# VIC-20_AV-Adaptor.net
KiCad netlist of a schematic drawn in EAGLE
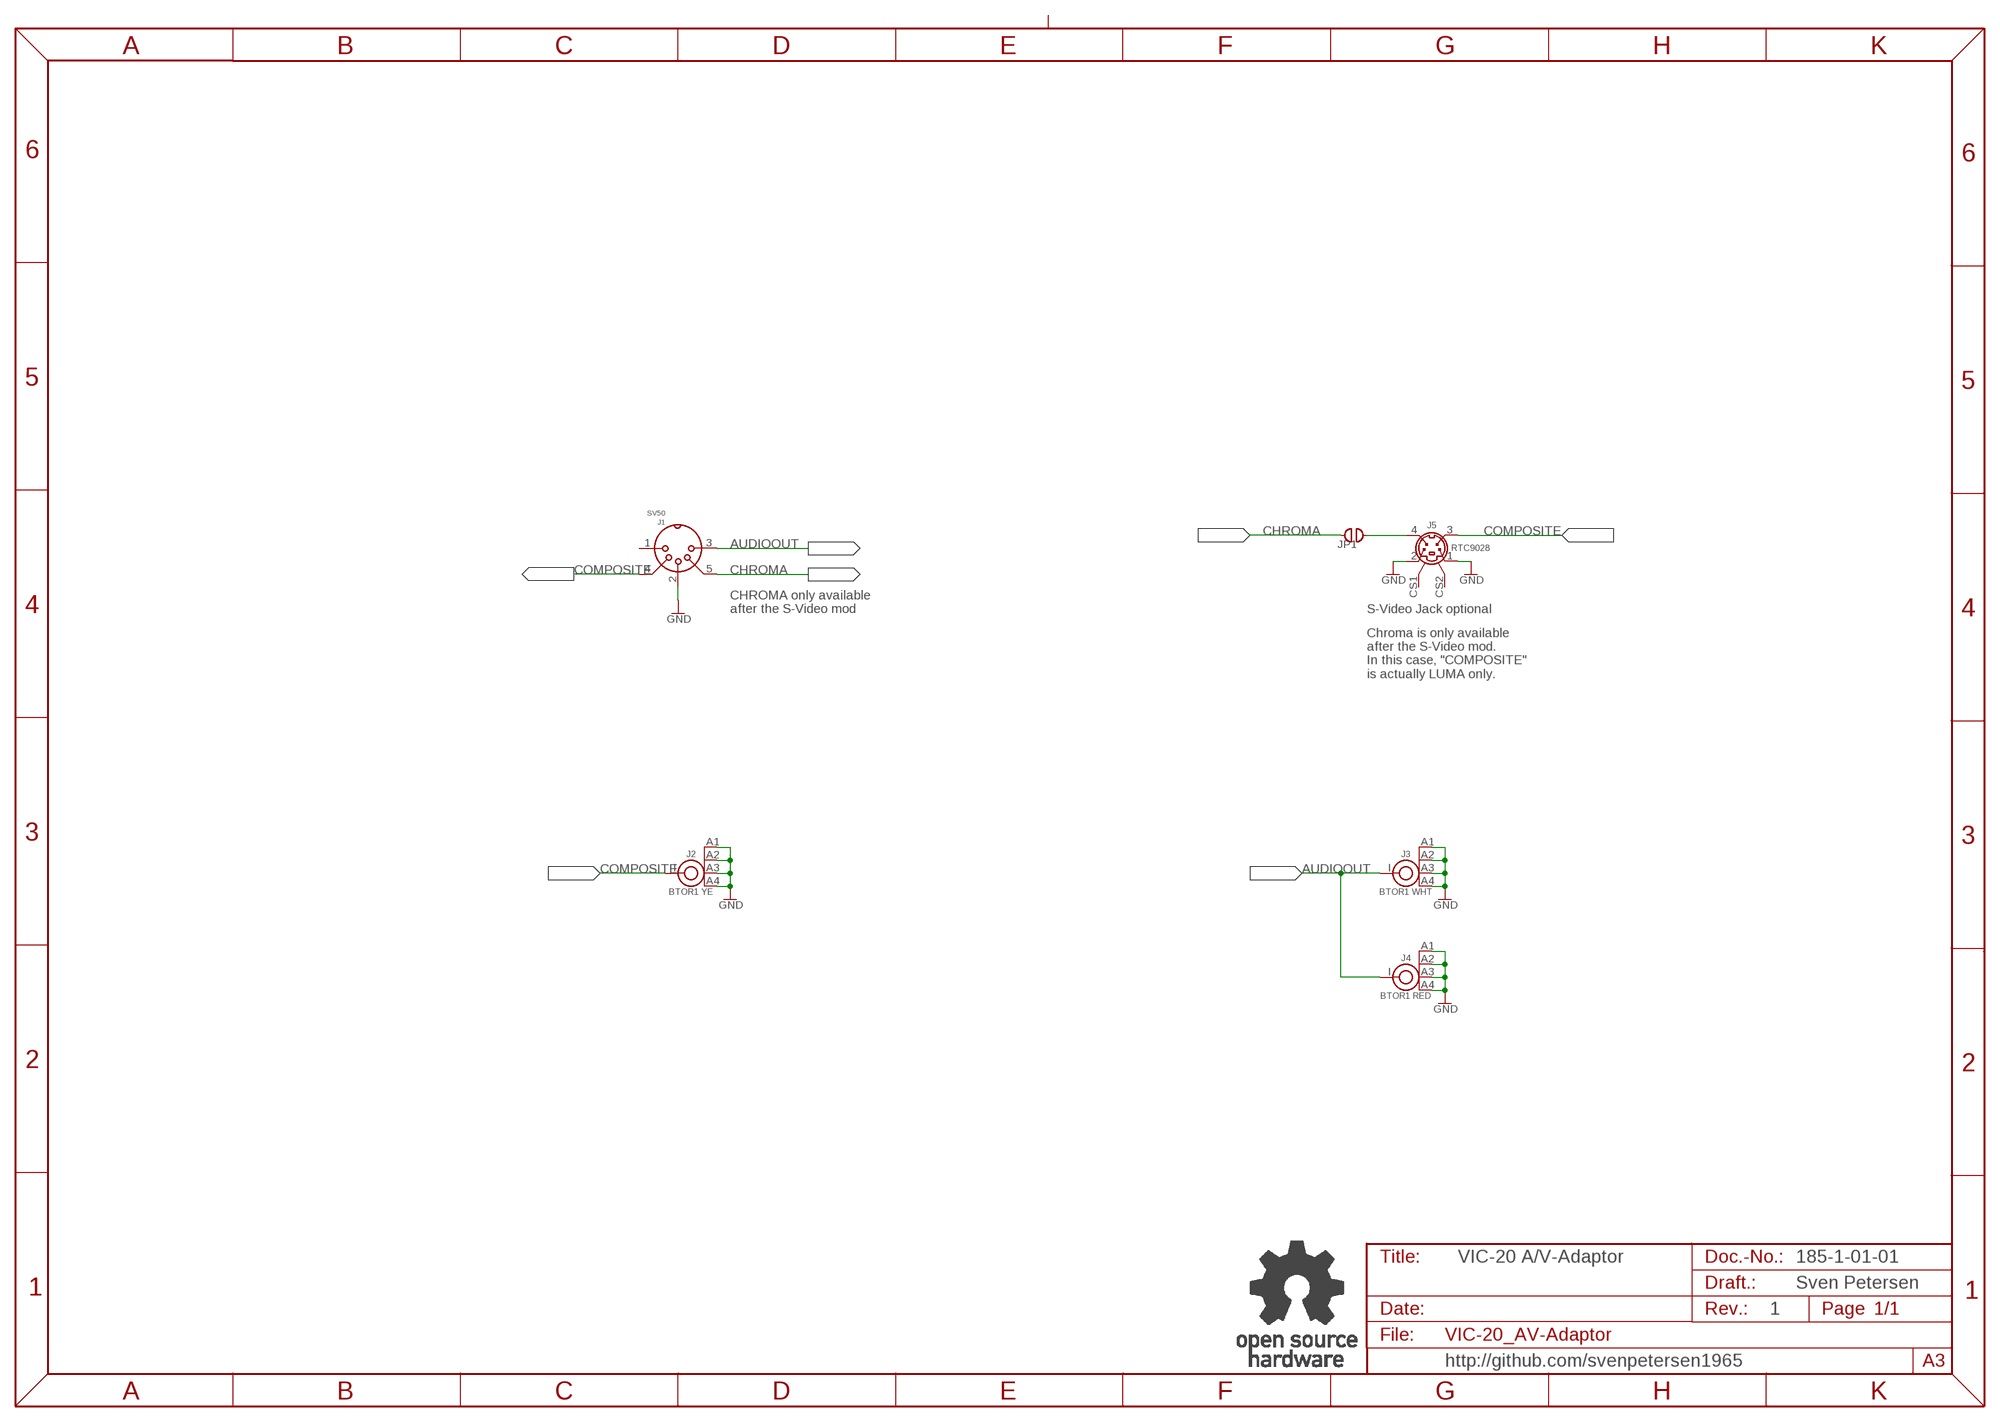
[diagram p0: schematic, sheet 1]

(export (version "E")
  (design (tool "Eeschema 10.0.6"))
  (components
    (comp (ref "J1")
      (value "SV50")
      (footprint "eagle-import:SV50_INNER")
      (libsource (lib "eagle-import") (part "SV50"))
    )
    (comp (ref "J2")
      (value "BTOR1 YE")
      (footprint "eagle-import:BTOR1")
      (libsource (lib "eagle-import") (part "BTOR1"))
    )
    (comp (ref "J3")
      (value "BTOR1 WHT")
      (footprint "eagle-import:BTOR1")
      (libsource (lib "eagle-import") (part "BTOR1"))
    )
    (comp (ref "J4")
      (value "BTOR1 RED")
      (footprint "eagle-import:BTOR1")
      (libsource (lib "eagle-import") (part "BTOR1"))
    )
    (comp (ref "J5")
      (value "RTC9028")
      (footprint "eagle-import:MINIDIN4_V")
      (libsource (lib "eagle-import") (part "RTC9028"))
    )
    (comp (ref "JP1")
      (value "COMBI_2P")
      (footprint "eagle-import:COMBI-2P")
      (libsource (lib "eagle-import") (part "COMBI_2P"))
    )
    (comp (ref "U$25")
      (value "OPEN_SOURCE_HW")
      (footprint "eagle-import:OPENHW")
      (libsource (lib "eagle-import") (part "OPEN_SOURCE_HW"))
    )
  )
  (nets
    (net (code "1") (name "/AUDIOOUT") (class "Default")
      (node (ref "J1") (pin "3") (pinfunction "3_3") (pintype "bidirectional"))
      (node (ref "J3") (pin "I") (pinfunction "I_I") (pintype "bidirectional"))
      (node (ref "J4") (pin "I") (pinfunction "I_I") (pintype "bidirectional"))
    )
    (net (code "2") (name "/CHROMA") (class "Default")
      (node (ref "J1") (pin "5") (pinfunction "5_5") (pintype "bidirectional"))
      (node (ref "JP1") (pin "1") (pinfunction "1_1") (pintype "passive"))
    )
    (net (code "3") (name "/COMPOSITE") (class "Default")
      (node (ref "J1") (pin "4") (pinfunction "4_4") (pintype "bidirectional"))
      (node (ref "J2") (pin "I") (pinfunction "I_I") (pintype "bidirectional"))
      (node (ref "J5") (pin "3") (pinfunction "3_3") (pintype "bidirectional"))
    )
    (net (code "4") (name "GND") (class "Default")
      (node (ref "J1") (pin "2") (pinfunction "2_2") (pintype "bidirectional"))
      (node (ref "J2") (pin "A1") (pinfunction "A1_A1") (pintype "bidirectional"))
      (node (ref "J2") (pin "A2") (pinfunction "A2_A2") (pintype "bidirectional"))
      (node (ref "J2") (pin "A3") (pinfunction "A3_A3") (pintype "bidirectional"))
      (node (ref "J2") (pin "A4") (pinfunction "A4_A4") (pintype "bidirectional"))
      (node (ref "J3") (pin "A1") (pinfunction "A1_A1") (pintype "bidirectional"))
      (node (ref "J3") (pin "A2") (pinfunction "A2_A2") (pintype "bidirectional"))
      (node (ref "J3") (pin "A3") (pinfunction "A3_A3") (pintype "bidirectional"))
      (node (ref "J3") (pin "A4") (pinfunction "A4_A4") (pintype "bidirectional"))
      (node (ref "J4") (pin "A1") (pinfunction "A1_A1") (pintype "bidirectional"))
      (node (ref "J4") (pin "A2") (pinfunction "A2_A2") (pintype "bidirectional"))
      (node (ref "J4") (pin "A3") (pinfunction "A3_A3") (pintype "bidirectional"))
      (node (ref "J4") (pin "A4") (pinfunction "A4_A4") (pintype "bidirectional"))
      (node (ref "J5") (pin "1") (pinfunction "1_1") (pintype "bidirectional"))
      (node (ref "J5") (pin "2") (pinfunction "2_2") (pintype "bidirectional"))
    )
    (net (code "5") (name "Net-(J5-Pad4)") (class "Default")
      (node (ref "J5") (pin "4") (pinfunction "4_4") (pintype "bidirectional"))
      (node (ref "JP1") (pin "2") (pinfunction "2_2") (pintype "passive"))
    )
    (net (code "6") (name "unconnected-(J1-Pad1)") (class "Default")
      (node (ref "J1") (pin "1") (pinfunction "1_1") (pintype "bidirectional"))
    )
    (net (code "7") (name "unconnected-(J5-PadCS1)") (class "Default")
      (node (ref "J5") (pin "CS1") (pinfunction "CS1_CS1") (pintype "bidirectional"))
    )
    (net (code "8") (name "unconnected-(J5-PadCS2)") (class "Default")
      (node (ref "J5") (pin "CS2") (pinfunction "CS2_CS2") (pintype "bidirectional"))
    )
  )
)
